# bms_GAUGE_R00.net
KiCad netlist of a schematic drawn in Altium Designer
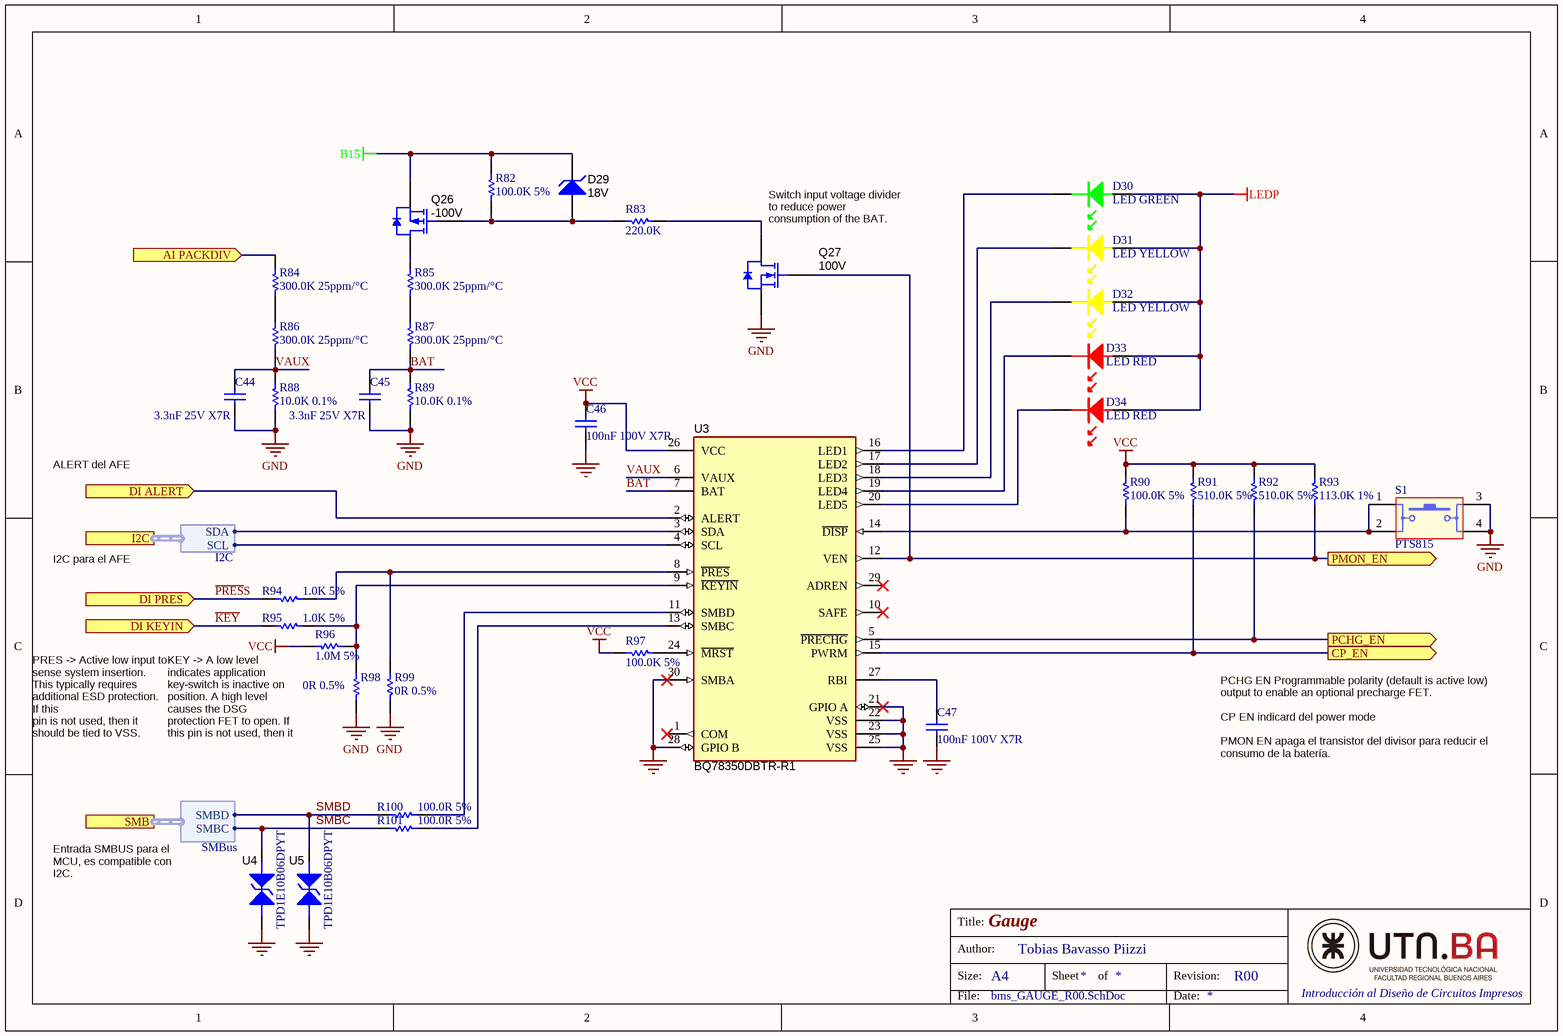
[diagram p0: bms_GAUGE_R00.SchDoc]

(export (version "E")
  (design (tool "Eeschema 10.0.6"))
  (components
    (comp (ref "C44")
      (value "3.3nF 25V X7R")
      (footprint "C0603")
      (description "Capacitor")
      (libsource (lib "capacitors") (part "Cap 0603"))
    )
    (comp (ref "C45")
      (value "3.3nF 25V X7R")
      (footprint "C0603")
      (description "Capacitor")
      (libsource (lib "capacitors") (part "Cap 0603"))
    )
    (comp (ref "C46")
      (value "100nF 100V X7R")
      (footprint "C0603")
      (description "Capacitor")
      (libsource (lib "capacitors") (part "Cap 0603"))
    )
    (comp (ref "C47")
      (value "100nF 100V X7R")
      (footprint "C0603")
      (description "Capacitor")
      (libsource (lib "capacitors") (part "Cap 0603"))
    )
    (comp (ref "D29")
      (value "18V")
      (footprint "sod-323")
      (description "Diode, Zener, 18 V, 200 mW, SOD-323")
      (fields
        (field (name "PARTNUMBER") "MMSZ5248BS-7-F")
        (field (name "MANUFACTURER") "Diodes Inc.")
        (field (name "SYMBOLCREATOR") "a0412235")
        (field (name "PUBLISHER") "Texas Instruments")
      )
      (libsource (lib "diodes") (part "MMSZ5248BS-7-F"))
    )
    (comp (ref "D30")
      (value "LED GREEN")
      (footprint "LED0603-G")
      (description "LED G")
      (libsource (lib "leds") (part "LED GREEN"))
    )
    (comp (ref "D31")
      (value "LED YELLOW")
      (footprint "LED0603-Y")
      (description "LED Y")
      (libsource (lib "leds") (part "LED YELLOW"))
    )
    (comp (ref "D32")
      (value "LED YELLOW")
      (footprint "LED0603-Y")
      (description "LED Y")
      (libsource (lib "leds") (part "LED YELLOW"))
    )
    (comp (ref "D33")
      (value "LED RED")
      (footprint "LED0603-R")
      (description "LED R")
      (libsource (lib "leds") (part "LED RED"))
    )
    (comp (ref "D34")
      (value "LED RED")
      (footprint "LED0603-R")
      (description "LED R")
      (libsource (lib "leds") (part "LED RED"))
    )
    (comp (ref "Q26")
      (value "-100V")
      (footprint "SOT-23")
      (description "MOSFET, P-CH, -100V, -0.6A, SOT-23")
      (fields
        (field (name "PARTNUMBER") "ZXMP10A13FTA")
        (field (name "MANUFACTURER") "Diodes Inc.")
        (field (name "PUBLISHER") "Texas Instruments")
      )
      (libsource (lib "pmos") (part "ZXMP10A13FTA"))
    )
    (comp (ref "Q27")
      (value "100V")
      (footprint "SOT-23")
      (description "MOSFET, N-CH, 100V, 0.17A, SOT-23")
      (fields
        (field (name "PARTNUMBER") "BSS123")
        (field (name "MANUFACTURER") "Fairchild Semiconductor")
        (field (name "PUBLISHER") "Texas Instruments")
      )
      (libsource (lib "nmos") (part "BSS123"))
    )
    (comp (ref "R82")
      (value "100.0K 5%")
      (footprint "R0603")
      (description "Resistor")
      (libsource (lib "resistors") (part "Res"))
    )
    (comp (ref "R83")
      (value "220.0K")
      (footprint "R0603")
      (description "Resistor")
      (libsource (lib "resistors") (part "Res"))
    )
    (comp (ref "R84")
      (value "300.0K 25ppm/°C")
      (footprint "R0603")
      (description "Resistor")
      (libsource (lib "resistors") (part "Res"))
    )
    (comp (ref "R85")
      (value "300.0K 25ppm/°C")
      (footprint "R0603")
      (description "Resistor")
      (libsource (lib "resistors") (part "Res"))
    )
    (comp (ref "R86")
      (value "300.0K 25ppm/°C")
      (footprint "R0603")
      (description "Resistor")
      (libsource (lib "resistors") (part "Res"))
    )
    (comp (ref "R87")
      (value "300.0K 25ppm/°C")
      (footprint "R0603")
      (description "Resistor")
      (libsource (lib "resistors") (part "Res"))
    )
    (comp (ref "R88")
      (value "10.0K 0.1%")
      (footprint "R0603")
      (description "Resistor")
      (libsource (lib "resistors") (part "Res"))
    )
    (comp (ref "R89")
      (value "10.0K 0.1%")
      (footprint "R0603")
      (description "Resistor")
      (libsource (lib "resistors") (part "Res"))
    )
    (comp (ref "R90")
      (value "100.0K 5%")
      (footprint "R0603")
      (description "Resistor")
      (libsource (lib "resistors") (part "Res"))
    )
    (comp (ref "R91")
      (value "510.0K 5%")
      (footprint "R0603")
      (description "Resistor")
      (libsource (lib "resistors") (part "Res"))
    )
    (comp (ref "R92")
      (value "510.0K 5%")
      (footprint "R0603")
      (description "Resistor")
      (libsource (lib "resistors") (part "Res"))
    )
    (comp (ref "R93")
      (value "113.0K 1%")
      (footprint "R0603")
      (description "Resistor")
      (libsource (lib "resistors") (part "Res"))
    )
    (comp (ref "R94")
      (value "1.0K 5%")
      (footprint "R0603")
      (description "Resistor")
      (libsource (lib "resistors") (part "Res"))
    )
    (comp (ref "R95")
      (value "1.0K 5%")
      (footprint "R0603")
      (description "Resistor")
      (libsource (lib "resistors") (part "Res"))
    )
    (comp (ref "R96")
      (value "1.0M 5%")
      (footprint "R0603")
      (description "Resistor")
      (libsource (lib "resistors") (part "Res"))
    )
    (comp (ref "R97")
      (value "100.0K 5%")
      (footprint "R0603")
      (description "Resistor")
      (libsource (lib "resistors") (part "Res"))
    )
    (comp (ref "R98")
      (value "0R 0.5%")
      (footprint "R0603")
      (description "Resistor")
      (libsource (lib "resistors") (part "Res"))
    )
    (comp (ref "R99")
      (value "0R 0.5%")
      (footprint "R0603")
      (description "Resistor")
      (libsource (lib "resistors") (part "Res"))
    )
    (comp (ref "R100")
      (value "100.0R 5%")
      (footprint "R0603")
      (description "Resistor")
      (libsource (lib "resistors") (part "Res"))
    )
    (comp (ref "R101")
      (value "100.0R 5%")
      (footprint "R0603")
      (description "Resistor")
      (libsource (lib "resistors") (part "Res"))
    )
    (comp (ref "S1")
      (value "PTS815")
      (footprint "PTS815SJK250SMTRLFS")
      (description "SWITCH TACTILE SPST-NO 0.05A 12V")
      (libsource (lib "connectors") (part "PTS815"))
    )
    (comp (ref "U3")
      (value "BQ78350DBTR-R1")
      (footprint "DBT0030A_N")
      (fields
        (field (name "ALTERNATE PARTNUMBER") "BQ78350DBT-R1")
        (field (name "MANUFACTURER") "Texas Instruments")
        (field (name "SYMBOLCREATOR") "x0208325")
        (field (name "PUBLISHER") "Texas Instruments")
      )
      (libsource (lib "integrated_circuits") (part "BQ78350DBTR-R1"))
    )
    (comp (ref "U4")
      (value "TPD1E10B06DPYT")
      (footprint "DPY0002A")
      (fields
        (field (name "MANUFACTURER") "Texas Instruments")
        (field (name "ALTERNATE PARTNUMBER") "Equivalent")
      )
      (libsource (lib "diodes") (part "TPD1E10B06DPYT"))
    )
    (comp (ref "U5")
      (value "TPD1E10B06DPYT")
      (footprint "DPY0002A")
      (fields
        (field (name "MANUFACTURER") "Texas Instruments")
        (field (name "ALTERNATE PARTNUMBER") "Equivalent")
      )
      (libsource (lib "diodes") (part "TPD1E10B06DPYT"))
    )
  )
  (nets
    (net (code "3") (name "/AI PACKDIV") (class "Default")
      (node (ref "R84") (pin "1") (pinfunction "1_1") (pintype "passive"))
    )
    (net (code "4") (name "/BAT") (class "Default")
      (node (ref "C45") (pin "2") (pinfunction "2_2") (pintype "passive"))
      (node (ref "R87") (pin "2") (pinfunction "2_2") (pintype "passive"))
      (node (ref "R89") (pin "1") (pinfunction "1_1") (pintype "passive"))
      (node (ref "U3") (pin "7") (pinfunction "BAT_7") (pintype "power_in"))
    )
    (net (code "5") (name "/CP_EN") (class "Default")
      (node (ref "R91") (pin "2") (pinfunction "2_2") (pintype "passive"))
      (node (ref "U3") (pin "15") (pinfunction "PWRM_15") (pintype "output"))
    )
    (net (code "6") (name "/DI ALERT") (class "Default")
      (node (ref "U3") (pin "2") (pinfunction "ALERT_2") (pintype "bidirectional"))
    )
    (net (code "7") (name "/PCHG_EN") (class "Default")
      (node (ref "R92") (pin "2") (pinfunction "2_2") (pintype "passive"))
      (node (ref "U3") (pin "5") (pinfunction "PRECHG_5") (pintype "output"))
    )
    (net (code "8") (name "/PMON_EN") (class "Default")
      (node (ref "Q27") (pin "1") (pinfunction "G_1") (pintype "passive"))
      (node (ref "R93") (pin "2") (pinfunction "2_2") (pintype "passive"))
      (node (ref "U3") (pin "12") (pinfunction "VEN_12") (pintype "output"))
    )
    (net (code "9") (name "/SCL") (class "Default")
      (node (ref "U3") (pin "4") (pinfunction "SCL_4") (pintype "bidirectional"))
    )
    (net (code "10") (name "/SDA") (class "Default")
      (node (ref "U3") (pin "3") (pinfunction "SDA_3") (pintype "bidirectional"))
    )
    (net (code "11") (name "/SMBC") (class "Default")
      (node (ref "R101") (pin "2") (pinfunction "2_2") (pintype "passive"))
      (node (ref "U4") (pin "2") (pinfunction "GND_2") (pintype "passive"))
    )
    (net (code "12") (name "/SMBD") (class "Default")
      (node (ref "R100") (pin "2") (pinfunction "2_2") (pintype "passive"))
      (node (ref "U5") (pin "2") (pinfunction "GND_2") (pintype "passive"))
    )
    (net (code "13") (name "/VAUX") (class "Default")
      (node (ref "C44") (pin "2") (pinfunction "2_2") (pintype "passive"))
      (node (ref "R86") (pin "2") (pinfunction "2_2") (pintype "passive"))
      (node (ref "R88") (pin "1") (pinfunction "1_1") (pintype "passive"))
      (node (ref "U3") (pin "6") (pinfunction "VAUX_6") (pintype "power_in"))
    )
    (net (code "16") (name "/~{KEY}") (class "Default")
      (node (ref "R95") (pin "2") (pinfunction "2_2") (pintype "passive"))
    )
    (net (code "17") (name "/~{PRES}S") (class "Default")
      (node (ref "R94") (pin "2") (pinfunction "2_2") (pintype "passive"))
    )
    (net (code "18") (name "B15") (class "Default")
      (node (ref "D29") (pin "1") (pinfunction "K_1") (pintype "passive"))
      (node (ref "Q26") (pin "2") (pinfunction "S_2") (pintype "passive"))
      (node (ref "R82") (pin "1") (pinfunction "1_1") (pintype "passive"))
    )
    (net (code "19") (name "GND") (class "Default")
      (node (ref "C44") (pin "1") (pinfunction "1_1") (pintype "passive"))
      (node (ref "C45") (pin "1") (pinfunction "1_1") (pintype "passive"))
      (node (ref "C46") (pin "1") (pinfunction "1_1") (pintype "passive"))
      (node (ref "C47") (pin "1") (pinfunction "1_1") (pintype "passive"))
      (node (ref "Q27") (pin "2") (pinfunction "S_2") (pintype "passive"))
      (node (ref "R88") (pin "2") (pinfunction "2_2") (pintype "passive"))
      (node (ref "R89") (pin "2") (pinfunction "2_2") (pintype "passive"))
      (node (ref "R98") (pin "2") (pinfunction "2_2") (pintype "passive"))
      (node (ref "R99") (pin "2") (pinfunction "2_2") (pintype "passive"))
      (node (ref "S1") (pin "3") (pinfunction "3_3") (pintype "passive"))
      (node (ref "S1") (pin "4") (pinfunction "4_4") (pintype "passive"))
      (node (ref "U3") (pin "21") (pinfunction "GPIO_A_21") (pintype "bidirectional"))
      (node (ref "U3") (pin "22") (pinfunction "VSS_22") (pintype "power_in"))
      (node (ref "U3") (pin "23") (pinfunction "VSS_23") (pintype "power_in"))
      (node (ref "U3") (pin "25") (pinfunction "VSS_25") (pintype "power_in"))
      (node (ref "U3") (pin "28") (pinfunction "GPIO_B_28") (pintype "bidirectional"))
      (node (ref "U3") (pin "30") (pinfunction "SMBA_30") (pintype "input"))
      (node (ref "U4") (pin "1") (pinfunction "IO_LINE_1") (pintype "passive"))
      (node (ref "U5") (pin "1") (pinfunction "IO_LINE_1") (pintype "passive"))
    )
    (net (code "20") (name "LEDP") (class "Default")
      (node (ref "D30") (pin "2") (pinfunction "A_2") (pintype "passive"))
      (node (ref "D31") (pin "2") (pinfunction "A_2") (pintype "passive"))
      (node (ref "D32") (pin "2") (pinfunction "A_2") (pintype "passive"))
      (node (ref "D33") (pin "2") (pinfunction "A_2") (pintype "passive"))
      (node (ref "D34") (pin "2") (pinfunction "A_2") (pintype "passive"))
    )
    (net (code "21") (name "Net-(D29-A)") (class "Default")
      (node (ref "D29") (pin "2") (pinfunction "A_2") (pintype "passive"))
      (node (ref "Q26") (pin "1") (pinfunction "G_1") (pintype "passive"))
      (node (ref "R82") (pin "2") (pinfunction "2_2") (pintype "passive"))
      (node (ref "R83") (pin "2") (pinfunction "2_2") (pintype "passive"))
    )
    (net (code "22") (name "Net-(D30-K)") (class "Default")
      (node (ref "D30") (pin "1") (pinfunction "K_1") (pintype "passive"))
      (node (ref "U3") (pin "16") (pinfunction "LED1_16") (pintype "output"))
    )
    (net (code "23") (name "Net-(D31-K)") (class "Default")
      (node (ref "D31") (pin "1") (pinfunction "K_1") (pintype "passive"))
      (node (ref "U3") (pin "17") (pinfunction "LED2_17") (pintype "output"))
    )
    (net (code "24") (name "Net-(D32-K)") (class "Default")
      (node (ref "D32") (pin "1") (pinfunction "K_1") (pintype "passive"))
      (node (ref "U3") (pin "18") (pinfunction "LED3_18") (pintype "output"))
    )
    (net (code "25") (name "Net-(D33-K)") (class "Default")
      (node (ref "D33") (pin "1") (pinfunction "K_1") (pintype "passive"))
      (node (ref "U3") (pin "19") (pinfunction "LED4_19") (pintype "output"))
    )
    (net (code "26") (name "Net-(D34-K)") (class "Default")
      (node (ref "D34") (pin "1") (pinfunction "K_1") (pintype "passive"))
      (node (ref "U3") (pin "20") (pinfunction "LED5_20") (pintype "output"))
    )
    (net (code "27") (name "Net-(Q26-D)") (class "Default")
      (node (ref "Q26") (pin "3") (pinfunction "D_3") (pintype "passive"))
      (node (ref "R85") (pin "1") (pinfunction "1_1") (pintype "passive"))
    )
    (net (code "28") (name "Net-(Q27-D)") (class "Default")
      (node (ref "Q27") (pin "3") (pinfunction "D_3") (pintype "passive"))
      (node (ref "R83") (pin "1") (pinfunction "1_1") (pintype "passive"))
    )
    (net (code "29") (name "Net-(R84-Pad2)") (class "Default")
      (node (ref "R84") (pin "2") (pinfunction "2_2") (pintype "passive"))
      (node (ref "R86") (pin "1") (pinfunction "1_1") (pintype "passive"))
    )
    (net (code "30") (name "Net-(R85-Pad2)") (class "Default")
      (node (ref "R85") (pin "2") (pinfunction "2_2") (pintype "passive"))
      (node (ref "R87") (pin "1") (pinfunction "1_1") (pintype "passive"))
    )
    (net (code "31") (name "Net-(U3-DISP)") (class "Default")
      (node (ref "R90") (pin "1") (pinfunction "1_1") (pintype "passive"))
      (node (ref "S1") (pin "1") (pinfunction "1_1") (pintype "passive"))
      (node (ref "S1") (pin "2") (pinfunction "2_2") (pintype "passive"))
      (node (ref "U3") (pin "14") (pinfunction "DISP_14") (pintype "input"))
    )
    (net (code "32") (name "Net-(U3-KEYIN)") (class "Default")
      (node (ref "R95") (pin "1") (pinfunction "1_1") (pintype "passive"))
      (node (ref "R96") (pin "2") (pinfunction "2_2") (pintype "passive"))
      (node (ref "R98") (pin "1") (pinfunction "1_1") (pintype "passive"))
      (node (ref "U3") (pin "9") (pinfunction "KEYIN_9") (pintype "input"))
    )
    (net (code "33") (name "Net-(U3-MRST)") (class "Default")
      (node (ref "R97") (pin "1") (pinfunction "1_1") (pintype "passive"))
      (node (ref "U3") (pin "24") (pinfunction "MRST_24") (pintype "input"))
    )
    (net (code "34") (name "Net-(U3-PRES)") (class "Default")
      (node (ref "R94") (pin "1") (pinfunction "1_1") (pintype "passive"))
      (node (ref "R99") (pin "1") (pinfunction "1_1") (pintype "passive"))
      (node (ref "U3") (pin "8") (pinfunction "PRES_8") (pintype "input"))
    )
    (net (code "35") (name "Net-(U3-RBI)") (class "Default")
      (node (ref "C47") (pin "2") (pinfunction "2_2") (pintype "passive"))
      (node (ref "U3") (pin "27") (pinfunction "RBI_27") (pintype "power_in"))
    )
    (net (code "36") (name "Net-(U3-SMBC)") (class "Default")
      (node (ref "R101") (pin "1") (pinfunction "1_1") (pintype "passive"))
      (node (ref "U3") (pin "13") (pinfunction "SMBC_13") (pintype "bidirectional"))
    )
    (net (code "37") (name "Net-(U3-SMBD)") (class "Default")
      (node (ref "R100") (pin "1") (pinfunction "1_1") (pintype "passive"))
      (node (ref "U3") (pin "11") (pinfunction "SMBD_11") (pintype "bidirectional"))
    )
    (net (code "38") (name "VCC") (class "Default")
      (node (ref "C46") (pin "2") (pinfunction "2_2") (pintype "passive"))
      (node (ref "R90") (pin "2") (pinfunction "2_2") (pintype "passive"))
      (node (ref "R91") (pin "1") (pinfunction "1_1") (pintype "passive"))
      (node (ref "R92") (pin "1") (pinfunction "1_1") (pintype "passive"))
      (node (ref "R93") (pin "1") (pinfunction "1_1") (pintype "passive"))
      (node (ref "R96") (pin "1") (pinfunction "1_1") (pintype "passive"))
      (node (ref "R97") (pin "2") (pinfunction "2_2") (pintype "passive"))
      (node (ref "U3") (pin "26") (pinfunction "VCC_26") (pintype "power_in"))
    )
    (net (code "39") (name "unconnected-(U3-ADREN-Pad29)") (class "Default")
      (node (ref "U3") (pin "29") (pinfunction "ADREN_29") (pintype "output+no_connect"))
    )
    (net (code "40") (name "unconnected-(U3-COM-Pad1)") (class "Default")
      (node (ref "U3") (pin "1") (pinfunction "COM_1") (pintype "output+no_connect"))
    )
    (net (code "41") (name "unconnected-(U3-SAFE-Pad10)") (class "Default")
      (node (ref "U3") (pin "10") (pinfunction "SAFE_10") (pintype "output+no_connect"))
    )
  )
)
